# Hall_sensor.net
KiCad netlist of a schematic drawn in Altium Designer
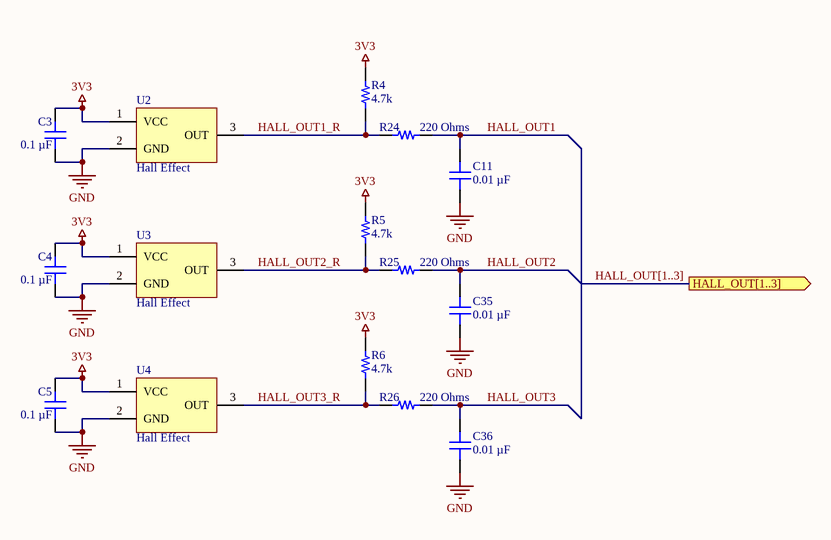
[diagram p0: Hall_sensor.SchDoc]

(export (version "E")
  (design (tool "Eeschema 10.0.6"))
  (components
    (comp (ref "C3")
      (value "0.1 µF")
      (footprint "CAP 0402_1005")
      (description "CAP CER 0.1UF 16V X7R 0402")
      (fields (field (name "PART NUMBER") "C0402C104K4RACAUTO") (field (name "MANUFACTURER") "KEMET"))
      (libsource (lib "Celestial Altium Library - altium_library") (part "Capacitor"))
    )
    (comp (ref "C4")
      (value "0.1 µF")
      (footprint "CAP 0402_1005")
      (description "CAP CER 0.1UF 16V X7R 0402")
      (fields (field (name "PART NUMBER") "C0402C104K4RACAUTO") (field (name "MANUFACTURER") "KEMET"))
      (libsource (lib "Celestial Altium Library - altium_library") (part "Capacitor"))
    )
    (comp (ref "C5")
      (value "0.1 µF")
      (footprint "CAP 0402_1005")
      (description "CAP CER 0.1UF 16V X7R 0402")
      (fields (field (name "PART NUMBER") "C0402C104K4RACAUTO") (field (name "MANUFACTURER") "KEMET"))
      (libsource (lib "Celestial Altium Library - altium_library") (part "Capacitor"))
    )
    (comp (ref "C11")
      (value "0.01 µF")
      (footprint "CAP 0402_1005")
      (description "CAP CER 0.1UF 16V X7R 0402")
      (fields (field (name "PART NUMBER") "C0402C104K4RACAUTO") (field (name "MANUFACTURER") "KEMET"))
      (libsource (lib "Celestial Altium Library - altium_library") (part "Capacitor"))
    )
    (comp (ref "C35")
      (value "0.01 µF")
      (footprint "CAP 0402_1005")
      (description "CAP CER 0.1UF 16V X7R 0402")
      (fields (field (name "PART NUMBER") "C0402C104K4RACAUTO") (field (name "MANUFACTURER") "KEMET"))
      (libsource (lib "Celestial Altium Library - altium_library") (part "Capacitor"))
    )
    (comp (ref "C36")
      (value "0.01 µF")
      (footprint "CAP 0402_1005")
      (description "CAP CER 0.1UF 16V X7R 0402")
      (fields (field (name "PART NUMBER") "C0402C104K4RACAUTO") (field (name "MANUFACTURER") "KEMET"))
      (libsource (lib "Celestial Altium Library - altium_library") (part "Capacitor"))
    )
    (comp (ref "R4")
      (value "4.7k")
      (footprint "RES 0402_1005")
      (description "RES 14.3K OHM 1% 1/10W 0402")
      (fields
        (field (name "PART NUMBER") "RK73H1ETTP1432F")
        (field (name "MANUFACTURER") "KOA Speer Electronics, Inc.")
      )
      (libsource (lib "Celestial Altium Library - altium_library") (part "Resistor"))
    )
    (comp (ref "R5")
      (value "4.7k")
      (footprint "RES 0402_1005")
      (description "RES 14.3K OHM 1% 1/10W 0402")
      (fields
        (field (name "PART NUMBER") "RK73H1ETTP1432F")
        (field (name "MANUFACTURER") "KOA Speer Electronics, Inc.")
      )
      (libsource (lib "Celestial Altium Library - altium_library") (part "Resistor"))
    )
    (comp (ref "R6")
      (value "4.7k")
      (footprint "RES 0402_1005")
      (description "RES 14.3K OHM 1% 1/10W 0402")
      (fields
        (field (name "PART NUMBER") "RK73H1ETTP1432F")
        (field (name "MANUFACTURER") "KOA Speer Electronics, Inc.")
      )
      (libsource (lib "Celestial Altium Library - altium_library") (part "Resistor"))
    )
    (comp (ref "R24")
      (value "220 Ohms")
      (footprint "RES 0402_1005")
      (description "RES 14.3K OHM 1% 1/10W 0402")
      (fields
        (field (name "PART NUMBER") "RK73H1ETTP1432F")
        (field (name "MANUFACTURER") "KOA Speer Electronics, Inc.")
      )
      (libsource (lib "Celestial Altium Library - altium_library") (part "Resistor"))
    )
    (comp (ref "R25")
      (value "220 Ohms")
      (footprint "RES 0402_1005")
      (description "RES 14.3K OHM 1% 1/10W 0402")
      (fields
        (field (name "PART NUMBER") "RK73H1ETTP1432F")
        (field (name "MANUFACTURER") "KOA Speer Electronics, Inc.")
      )
      (libsource (lib "Celestial Altium Library - altium_library") (part "Resistor"))
    )
    (comp (ref "R26")
      (value "220 Ohms")
      (footprint "RES 0402_1005")
      (description "RES 14.3K OHM 1% 1/10W 0402")
      (fields
        (field (name "PART NUMBER") "RK73H1ETTP1432F")
        (field (name "MANUFACTURER") "KOA Speer Electronics, Inc.")
      )
      (libsource (lib "Celestial Altium Library - altium_library") (part "Resistor"))
    )
    (comp (ref "U2") (value "Hall Effect") (footprint "DRV5011ADLPG") (libsource (lib "IC") (part "DRV5011")))
    (comp (ref "U3") (value "Hall Effect") (footprint "DRV5011ADLPG") (libsource (lib "IC") (part "DRV5011")))
    (comp (ref "U4") (value "Hall Effect") (footprint "DRV5011ADLPG") (libsource (lib "IC") (part "DRV5011")))
  )
  (nets
    (net (code "1") (name "/HALL_OUT1") (class "Default")
      (node (ref "C11") (pin "1") (pinfunction "1_1") (pintype "passive"))
      (node (ref "R24") (pin "2") (pinfunction "2_2") (pintype "passive"))
    )
    (net (code "2") (name "/HALL_OUT1_R") (class "Default")
      (node (ref "R24") (pin "1") (pinfunction "1_1") (pintype "passive"))
      (node (ref "R4") (pin "2") (pinfunction "2_2") (pintype "passive"))
      (node (ref "U2") (pin "3") (pinfunction "OUT_3") (pintype "passive"))
    )
    (net (code "3") (name "/HALL_OUT2") (class "Default")
      (node (ref "C35") (pin "1") (pinfunction "1_1") (pintype "passive"))
      (node (ref "R25") (pin "2") (pinfunction "2_2") (pintype "passive"))
    )
    (net (code "4") (name "/HALL_OUT2_R") (class "Default")
      (node (ref "R25") (pin "1") (pinfunction "1_1") (pintype "passive"))
      (node (ref "R5") (pin "2") (pinfunction "2_2") (pintype "passive"))
      (node (ref "U3") (pin "3") (pinfunction "OUT_3") (pintype "passive"))
    )
    (net (code "5") (name "/HALL_OUT3") (class "Default")
      (node (ref "C36") (pin "1") (pinfunction "1_1") (pintype "passive"))
      (node (ref "R26") (pin "2") (pinfunction "2_2") (pintype "passive"))
    )
    (net (code "6") (name "/HALL_OUT3_R") (class "Default")
      (node (ref "R26") (pin "1") (pinfunction "1_1") (pintype "passive"))
      (node (ref "R6") (pin "2") (pinfunction "2_2") (pintype "passive"))
      (node (ref "U4") (pin "3") (pinfunction "OUT_3") (pintype "passive"))
    )
    (net (code "8") (name "3V3") (class "Default")
      (node (ref "C3") (pin "1") (pinfunction "1_1") (pintype "passive"))
      (node (ref "C4") (pin "1") (pinfunction "1_1") (pintype "passive"))
      (node (ref "C5") (pin "1") (pinfunction "1_1") (pintype "passive"))
      (node (ref "R4") (pin "1") (pinfunction "1_1") (pintype "passive"))
      (node (ref "R5") (pin "1") (pinfunction "1_1") (pintype "passive"))
      (node (ref "R6") (pin "1") (pinfunction "1_1") (pintype "passive"))
      (node (ref "U2") (pin "1") (pinfunction "VCC_1") (pintype "passive"))
      (node (ref "U3") (pin "1") (pinfunction "VCC_1") (pintype "passive"))
      (node (ref "U4") (pin "1") (pinfunction "VCC_1") (pintype "passive"))
    )
    (net (code "9") (name "GND") (class "Default")
      (node (ref "C11") (pin "2") (pinfunction "2_2") (pintype "passive"))
      (node (ref "C3") (pin "2") (pinfunction "2_2") (pintype "passive"))
      (node (ref "C35") (pin "2") (pinfunction "2_2") (pintype "passive"))
      (node (ref "C36") (pin "2") (pinfunction "2_2") (pintype "passive"))
      (node (ref "C4") (pin "2") (pinfunction "2_2") (pintype "passive"))
      (node (ref "C5") (pin "2") (pinfunction "2_2") (pintype "passive"))
      (node (ref "U2") (pin "2") (pinfunction "GND_2") (pintype "passive"))
      (node (ref "U3") (pin "2") (pinfunction "GND_2") (pintype "passive"))
      (node (ref "U4") (pin "2") (pinfunction "GND_2") (pintype "passive"))
    )
  )
)
